# Sch_Sensores.net
KiCad netlist of a schematic drawn in Altium Designer
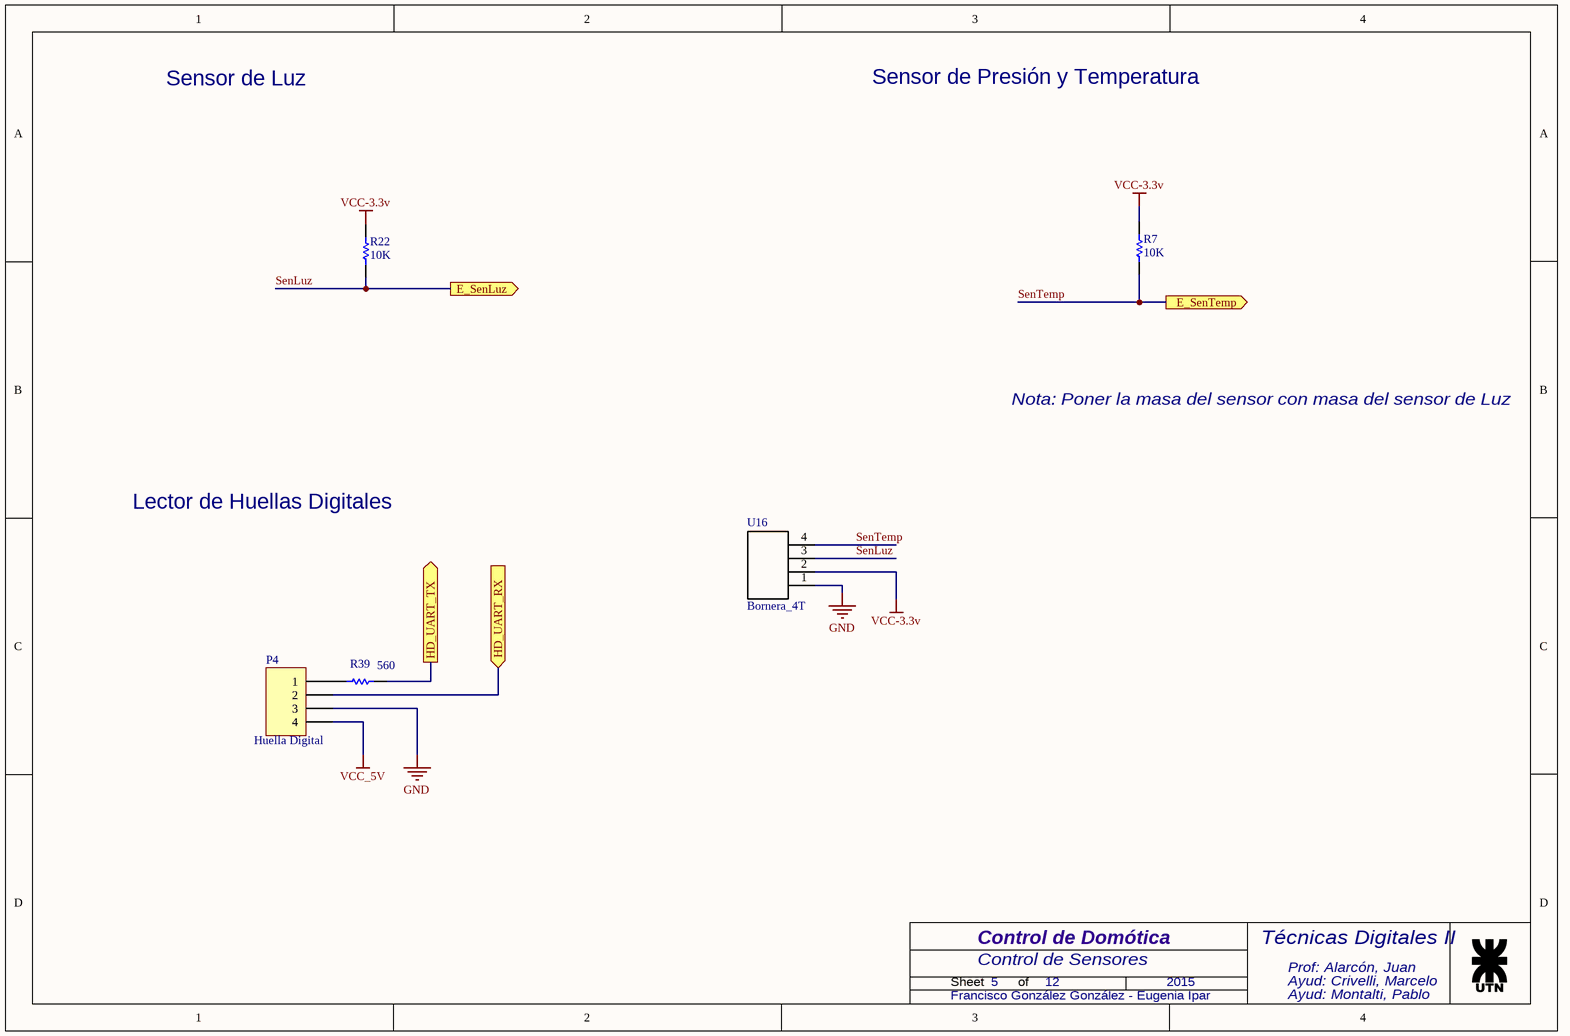
[diagram p0: Sch_Sensores.SchDoc]

(export (version "E")
  (design (tool "Eeschema 10.0.6"))
  (components
    (comp (ref "P4")
      (value "Huella Digital")
      (footprint "HDR1X4")
      (description "Header, 4-Pin")
      (fields (field (name "PUBLISHER") "Altium Limited"))
      (libsource (lib "Miscellaneous Connectors") (part "Header 4"))
    )
    (comp (ref "R7")
      (value "10K")
      (footprint "AXIAL-0.3")
      (description "Resistor")
      (fields (field (name "Comment") "Res1") (field (name "PUBLISHER") "Altium Limited"))
      (libsource (lib "Miscellaneous Devices") (part "Res1"))
    )
    (comp (ref "R22")
      (value "10K")
      (footprint "AXIAL-0.3")
      (description "Resistor")
      (fields (field (name "Comment") "Res1") (field (name "PUBLISHER") "Altium Limited"))
      (libsource (lib "Miscellaneous Devices") (part "Res1"))
    )
    (comp (ref "R39")
      (value "560")
      (footprint "AXIAL-0.3")
      (description "Resistor")
      (fields (field (name "Comment") "Res1") (field (name "PUBLISHER") "Altium Limited"))
      (libsource (lib "Miscellaneous Devices") (part "Res1"))
    )
    (comp (ref "U16")
      (value "Bornera_4T")
      (footprint "BORNERA_4")
      (description "Bornera de 4 Terminales Pitch 5mm")
      (libsource (lib "Ampli_Lib_Sch") (part "Bornera_4T"))
    )
  )
  (nets
    (net (code "1") (name "/HD_UART_RX") (class "Default")
      (node (ref "P4") (pin "2") (pinfunction "2_2") (pintype "passive"))
    )
    (net (code "2") (name "/HD_UART_TX") (class "Default")
      (node (ref "R39") (pin "1") (pinfunction "1_1") (pintype "passive"))
    )
    (net (code "3") (name "/SenLuz") (class "Default")
      (node (ref "R22") (pin "1") (pinfunction "1_1") (pintype "passive"))
      (node (ref "U16") (pin "3") (pinfunction "3_3") (pintype "passive"))
    )
    (net (code "4") (name "/SenTemp") (class "Default")
      (node (ref "R7") (pin "1") (pinfunction "1_1") (pintype "passive"))
      (node (ref "U16") (pin "4") (pinfunction "4_4") (pintype "passive"))
    )
    (net (code "5") (name "GND") (class "Default")
      (node (ref "P4") (pin "3") (pinfunction "3_3") (pintype "passive"))
      (node (ref "U16") (pin "1") (pinfunction "1_1") (pintype "passive"))
    )
    (net (code "6") (name "Net-(P4-Pad1)") (class "Default")
      (node (ref "P4") (pin "1") (pinfunction "1_1") (pintype "passive"))
      (node (ref "R39") (pin "2") (pinfunction "2_2") (pintype "passive"))
    )
    (net (code "7") (name "VCC-3.3v") (class "Default")
      (node (ref "R22") (pin "2") (pinfunction "2_2") (pintype "passive"))
      (node (ref "R7") (pin "2") (pinfunction "2_2") (pintype "passive"))
      (node (ref "U16") (pin "2") (pinfunction "2_2") (pintype "passive"))
    )
    (net (code "8") (name "VCC_5V") (class "Default")
      (node (ref "P4") (pin "4") (pinfunction "4_4") (pintype "passive"))
    )
  )
)
